# RP2040-M2-B-M-key.net
KiCad netlist of a schematic drawn in EAGLE
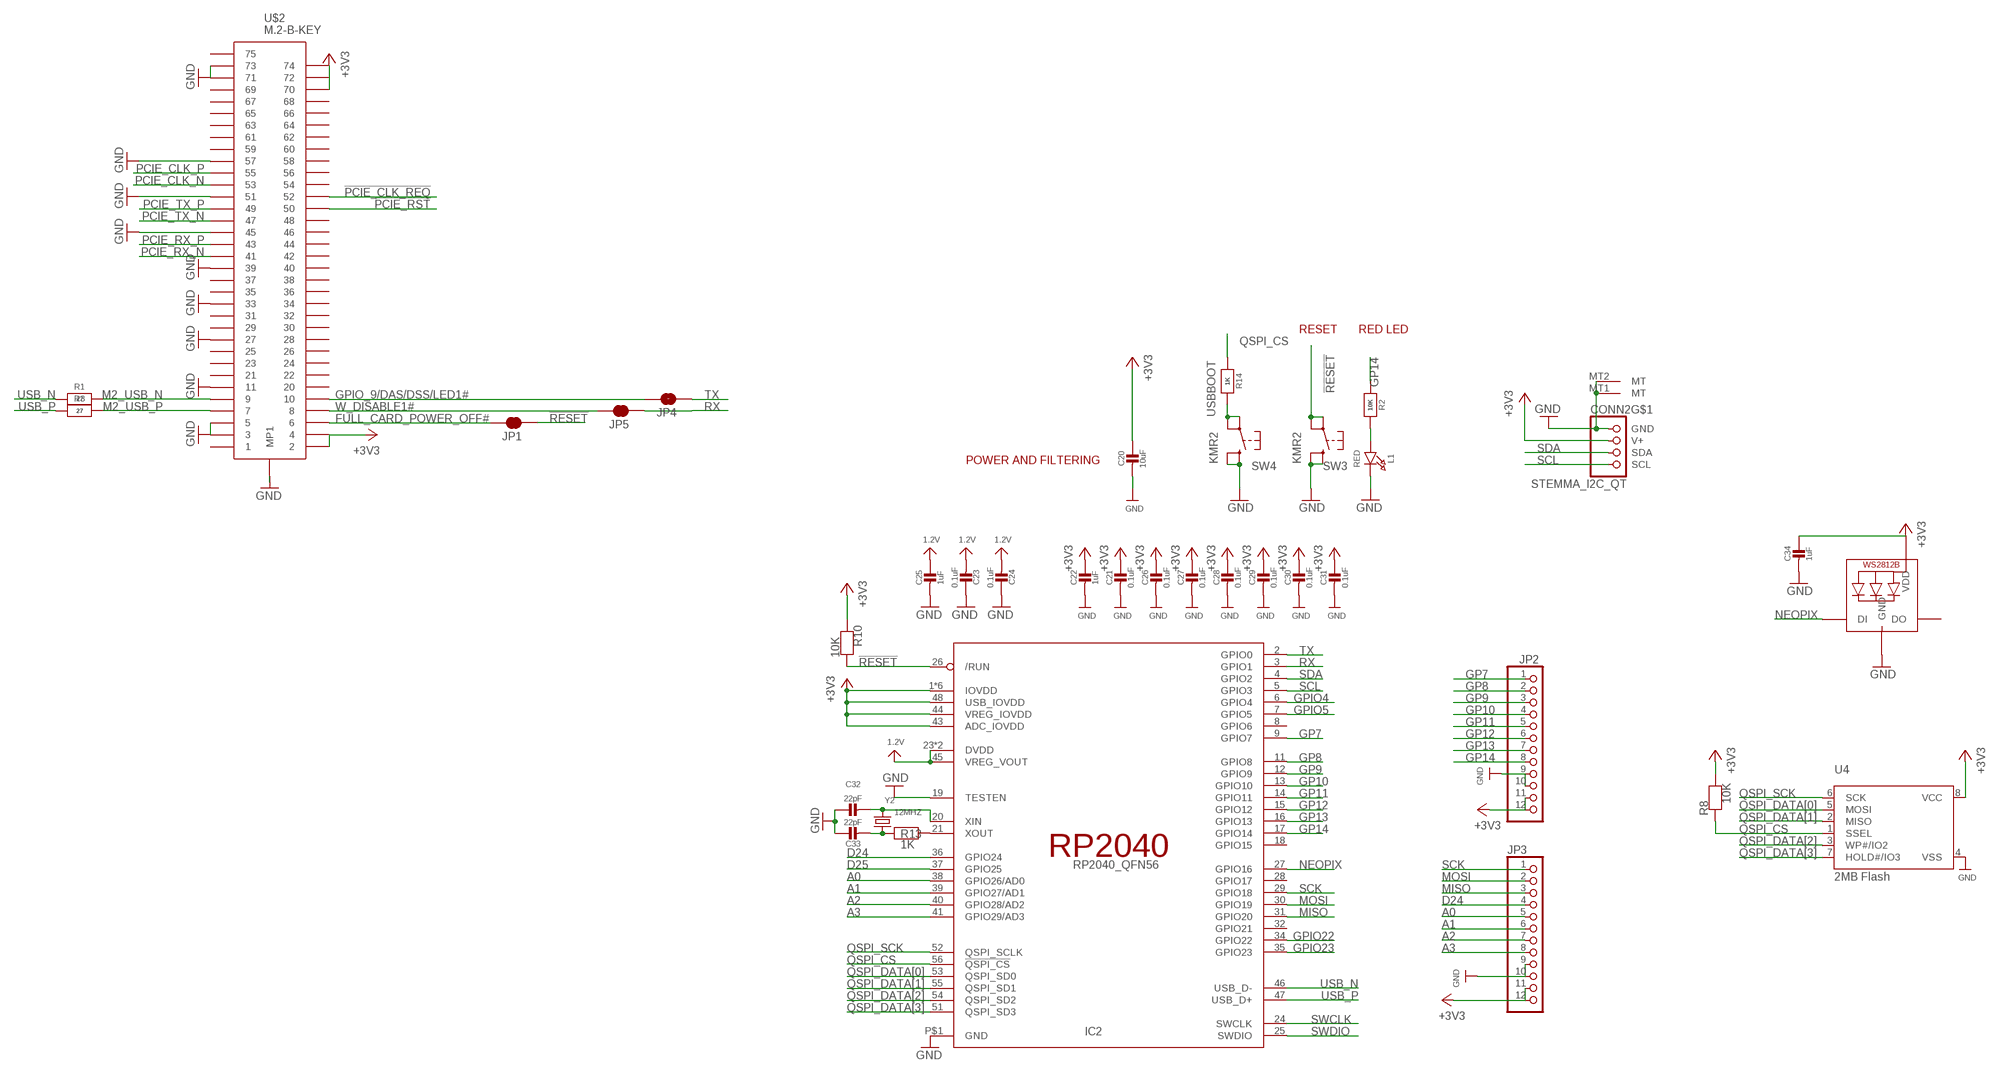
[diagram p0: schematic, sheet 1]

(export (version "E")
  (design (tool "Eeschema 10.0.6"))
  (components
    (comp (ref "C20")
      (value "10uF")
      (footprint "eagle-import:0805-NO")
      (libsource (lib "eagle-import") (part "CAP_CERAMIC0805-NOOUTLINE"))
    )
    (comp (ref "C21")
      (value "0.1uF")
      (footprint "eagle-import:_0402MP")
      (libsource (lib "eagle-import") (part "microbuilder_25095254_CAP_CERAMIC_0402MP"))
    )
    (comp (ref "C22")
      (value "1uF")
      (footprint "eagle-import:_0402MP")
      (libsource (lib "eagle-import") (part "microbuilder_25095254_CAP_CERAMIC_0402MP"))
    )
    (comp (ref "C23")
      (value "0.1uF")
      (footprint "eagle-import:_0402MP")
      (libsource (lib "eagle-import") (part "microbuilder_25095254_CAP_CERAMIC_0402MP"))
    )
    (comp (ref "C24")
      (value "0.1uF")
      (footprint "eagle-import:_0402MP")
      (libsource (lib "eagle-import") (part "microbuilder_25095254_CAP_CERAMIC_0402MP"))
    )
    (comp (ref "C25")
      (value "1uF")
      (footprint "eagle-import:_0402MP")
      (libsource (lib "eagle-import") (part "microbuilder_25095254_CAP_CERAMIC_0402MP"))
    )
    (comp (ref "C26")
      (value "0.1uF")
      (footprint "eagle-import:_0402MP")
      (libsource (lib "eagle-import") (part "microbuilder_25095254_CAP_CERAMIC_0402MP"))
    )
    (comp (ref "C27")
      (value "0.1uF")
      (footprint "eagle-import:_0402MP")
      (libsource (lib "eagle-import") (part "microbuilder_25095254_CAP_CERAMIC_0402MP"))
    )
    (comp (ref "C28")
      (value "0.1uF")
      (footprint "eagle-import:_0402MP")
      (libsource (lib "eagle-import") (part "microbuilder_25095254_CAP_CERAMIC_0402MP"))
    )
    (comp (ref "C29")
      (value "0.1uF")
      (footprint "eagle-import:_0402MP")
      (libsource (lib "eagle-import") (part "microbuilder_25095254_CAP_CERAMIC_0402MP"))
    )
    (comp (ref "C30")
      (value "0.1uF")
      (footprint "eagle-import:_0402MP")
      (libsource (lib "eagle-import") (part "microbuilder_25095254_CAP_CERAMIC_0402MP"))
    )
    (comp (ref "C31")
      (value "0.1uF")
      (footprint "eagle-import:_0402MP")
      (libsource (lib "eagle-import") (part "microbuilder_25095254_CAP_CERAMIC_0402MP"))
    )
    (comp (ref "C32")
      (value "22pF")
      (footprint "eagle-import:_0402MP")
      (libsource (lib "eagle-import") (part "microbuilder_25095254_CAP_CERAMIC_0402MP"))
    )
    (comp (ref "C33")
      (value "22pF")
      (footprint "eagle-import:_0402MP")
      (libsource (lib "eagle-import") (part "microbuilder_25095254_CAP_CERAMIC_0402MP"))
    )
    (comp (ref "C34")
      (value "1uF")
      (footprint "eagle-import:_0402MP")
      (libsource (lib "eagle-import") (part "microbuilder_25095254_CAP_CERAMIC_0402MP"))
    )
    (comp (ref "CONN2")
      (value "STEMMA_I2C_QT")
      (footprint "eagle-import:JST_SH4")
      (libsource (lib "eagle-import") (part "STEMMA_I2C_QT"))
    )
    (comp (ref "IC2")
      (value "RP2040_QFN56")
      (footprint "eagle-import:QFN56_7MM_REDUCEDEPAD")
      (libsource (lib "eagle-import") (part "RP2040_QFN56"))
    )
    (comp (ref "JP1")
      (value "JUMPER-SMT_2_NC_TRACE_NO-SILK")
      (footprint "eagle-import:SMT-JUMPER_2_NC_TRACE_NO-SILK")
      (libsource (lib "eagle-import") (part "JUMPER-SMT_2_NC_TRACE_NO-SILK"))
    )
    (comp (ref "JP2")
      (value "HEADER-1X12")
      (footprint "eagle-import:1X12_ROUND")
      (libsource (lib "eagle-import") (part "HEADER-1X12"))
    )
    (comp (ref "JP3")
      (value "HEADER-1X12")
      (footprint "eagle-import:1X12_ROUND")
      (libsource (lib "eagle-import") (part "HEADER-1X12"))
    )
    (comp (ref "JP4")
      (value "JUMPER-SMT_2_NC_TRACE_NO-SILK")
      (footprint "eagle-import:SMT-JUMPER_2_NC_TRACE_NO-SILK")
      (libsource (lib "eagle-import") (part "JUMPER-SMT_2_NC_TRACE_NO-SILK"))
    )
    (comp (ref "JP5")
      (value "JUMPER-SMT_2_NC_TRACE_NO-SILK")
      (footprint "eagle-import:SMT-JUMPER_2_NC_TRACE_NO-SILK")
      (libsource (lib "eagle-import") (part "JUMPER-SMT_2_NC_TRACE_NO-SILK"))
    )
    (comp (ref "L1")
      (value "RED")
      (footprint "eagle-import:CHIPLED_0603_NOOUTLINE")
      (libsource (lib "eagle-import") (part "LED0603_NOOUTLINE"))
    )
    (comp (ref "LED2")
      (value "WS2812B3535")
      (footprint "eagle-import:LED3535")
      (libsource (lib "eagle-import") (part "WS2812B3535"))
    )
    (comp (ref "R1")
      (value "27")
      (footprint "eagle-import:_0402MP")
      (libsource (lib "eagle-import") (part "RESISTOR_0402MP"))
    )
    (comp (ref "R2")
      (value "10K")
      (footprint "eagle-import:_0402MP")
      (libsource (lib "eagle-import") (part "RESISTOR_0402MP"))
    )
    (comp (ref "R3")
      (value "27")
      (footprint "eagle-import:_0402MP")
      (libsource (lib "eagle-import") (part "RESISTOR_0402MP"))
    )
    (comp (ref "R8")
      (value "10K")
      (footprint "eagle-import:_0402MP")
      (libsource (lib "eagle-import") (part "RESISTOR_0402MP"))
    )
    (comp (ref "R10")
      (value "10K")
      (footprint "eagle-import:_0402MP")
      (libsource (lib "eagle-import") (part "RESISTOR_0402MP"))
    )
    (comp (ref "R13")
      (value "1K")
      (footprint "eagle-import:_0402MP")
      (libsource (lib "eagle-import") (part "RESISTOR_0402MP"))
    )
    (comp (ref "R14")
      (value "1K")
      (footprint "eagle-import:_0402MP")
      (libsource (lib "eagle-import") (part "RESISTOR_0402MP"))
    )
    (comp (ref "SW3")
      (value "KMR2")
      (footprint "eagle-import:BTN_KMR2_4.6X2.8")
      (libsource (lib "eagle-import") (part "SWITCH_TACT_SMT4.6X2.8"))
    )
    (comp (ref "SW4")
      (value "KMR2")
      (footprint "eagle-import:BTN_KMR2_4.6X2.8")
      (libsource (lib "eagle-import") (part "SWITCH_TACT_SMT4.6X2.8"))
    )
    (comp (ref "U$2")
      (value "M.2-B-KEY")
      (footprint "eagle-import:M.2-B-KEY")
      (libsource (lib "eagle-import") (part "M.2-B-KEY"))
    )
    (comp (ref "U4")
      (value "2MB Flash")
      (footprint "eagle-import:SOIC8_208MIL")
      (libsource (lib "eagle-import") (part "SPIFLASH_8PIN208MIL"))
    )
    (comp (ref "Y2")
      (value "12MHZ")
      (footprint "eagle-import:CRYSTAL_3.2X2.5")
      (libsource (lib "eagle-import") (part "CRYSTALTHIN"))
    )
  )
  (nets
    (net (code "1") (name "+3V3") (class "Default")
      (node (ref "C20") (pin "1") (pinfunction "1_1") (pintype "passive"))
      (node (ref "C21") (pin "1") (pinfunction "P$1_1") (pintype "passive"))
      (node (ref "C22") (pin "1") (pinfunction "P$1_1") (pintype "passive"))
      (node (ref "C26") (pin "1") (pinfunction "P$1_1") (pintype "passive"))
      (node (ref "C27") (pin "1") (pinfunction "P$1_1") (pintype "passive"))
      (node (ref "C28") (pin "1") (pinfunction "P$1_1") (pintype "passive"))
      (node (ref "C29") (pin "1") (pinfunction "P$1_1") (pintype "passive"))
      (node (ref "C30") (pin "1") (pinfunction "P$1_1") (pintype "passive"))
      (node (ref "C31") (pin "1") (pinfunction "P$1_1") (pintype "passive"))
      (node (ref "C34") (pin "1") (pinfunction "P$1_1") (pintype "passive"))
      (node (ref "CONN2") (pin "2") (pinfunction "V+_2") (pintype "passive"))
      (node (ref "IC2") (pin "1") (pinfunction "IOVDD_1") (pintype "power_in"))
      (node (ref "IC2") (pin "10") (pinfunction "IOVDD_10") (pintype "power_in"))
      (node (ref "IC2") (pin "22") (pinfunction "IOVDD_22") (pintype "power_in"))
      (node (ref "IC2") (pin "33") (pinfunction "IOVDD_33") (pintype "power_in"))
      (node (ref "IC2") (pin "42") (pinfunction "IOVDD_42") (pintype "power_in"))
      (node (ref "IC2") (pin "43") (pinfunction "ADC_IOVDD_43") (pintype "power_in"))
      (node (ref "IC2") (pin "44") (pinfunction "VREG_IOVDD_44") (pintype "power_in"))
      (node (ref "IC2") (pin "48") (pinfunction "USB_IOVDD_48") (pintype "power_in"))
      (node (ref "IC2") (pin "49") (pinfunction "IOVDD_49") (pintype "power_in"))
      (node (ref "JP2") (pin "11") (pinfunction "11_11") (pintype "passive"))
      (node (ref "JP2") (pin "12") (pinfunction "12_12") (pintype "passive"))
      (node (ref "JP3") (pin "11") (pinfunction "11_11") (pintype "passive"))
      (node (ref "JP3") (pin "12") (pinfunction "12_12") (pintype "passive"))
      (node (ref "LED2") (pin "2") (pinfunction "VDD_2") (pintype "power_in"))
      (node (ref "R10") (pin "1") (pinfunction "1_1") (pintype "passive"))
      (node (ref "R8") (pin "2") (pinfunction "2_2") (pintype "passive"))
      (node (ref "U$2") (pin "P$2") (pinfunction "2_P$2") (pintype "bidirectional"))
      (node (ref "U$2") (pin "P$4") (pinfunction "4_P$4") (pintype "bidirectional"))
      (node (ref "U$2") (pin "P$70") (pinfunction "70_P$70") (pintype "bidirectional"))
      (node (ref "U$2") (pin "P$72") (pinfunction "72_P$72") (pintype "bidirectional"))
      (node (ref "U$2") (pin "P$74") (pinfunction "74_P$74") (pintype "bidirectional"))
      (node (ref "U4") (pin "8") (pinfunction "VCC_8") (pintype "bidirectional"))
    )
    (net (code "2") (name "/A0") (class "Default")
      (node (ref "IC2") (pin "38") (pinfunction "GPIO26/AD0_38") (pintype "bidirectional"))
      (node (ref "JP3") (pin "5") (pinfunction "5_5") (pintype "passive"))
    )
    (net (code "3") (name "/A1") (class "Default")
      (node (ref "IC2") (pin "39") (pinfunction "GPIO27/AD1_39") (pintype "bidirectional"))
      (node (ref "JP3") (pin "6") (pinfunction "6_6") (pintype "passive"))
    )
    (net (code "4") (name "/A2") (class "Default")
      (node (ref "IC2") (pin "40") (pinfunction "GPIO28/AD2_40") (pintype "bidirectional"))
      (node (ref "JP3") (pin "7") (pinfunction "7_7") (pintype "passive"))
    )
    (net (code "5") (name "/A3") (class "Default")
      (node (ref "IC2") (pin "41") (pinfunction "GPIO29/AD3_41") (pintype "bidirectional"))
      (node (ref "JP3") (pin "8") (pinfunction "8_8") (pintype "passive"))
    )
    (net (code "6") (name "/D24") (class "Default")
      (node (ref "IC2") (pin "36") (pinfunction "GPIO24_36") (pintype "bidirectional"))
      (node (ref "JP3") (pin "4") (pinfunction "4_4") (pintype "passive"))
    )
    (net (code "7") (name "/D25") (class "Default")
      (node (ref "IC2") (pin "37") (pinfunction "GPIO25_37") (pintype "bidirectional"))
    )
    (net (code "8") (name "/FULL_CARD_POWER_OFF#") (class "Default")
      (node (ref "JP1") (pin "1") (pinfunction "1_1") (pintype "passive"))
      (node (ref "U$2") (pin "P$6") (pinfunction "6_P$6") (pintype "bidirectional"))
    )
    (net (code "9") (name "/GP7") (class "Default")
      (node (ref "IC2") (pin "9") (pinfunction "GPIO7_9") (pintype "bidirectional"))
      (node (ref "JP2") (pin "1") (pinfunction "1_1") (pintype "passive"))
    )
    (net (code "10") (name "/GP8") (class "Default")
      (node (ref "IC2") (pin "11") (pinfunction "GPIO8_11") (pintype "bidirectional"))
      (node (ref "JP2") (pin "2") (pinfunction "2_2") (pintype "passive"))
    )
    (net (code "11") (name "/GP9") (class "Default")
      (node (ref "IC2") (pin "12") (pinfunction "GPIO9_12") (pintype "bidirectional"))
      (node (ref "JP2") (pin "3") (pinfunction "3_3") (pintype "passive"))
    )
    (net (code "12") (name "/GP10") (class "Default")
      (node (ref "IC2") (pin "13") (pinfunction "GPIO10_13") (pintype "bidirectional"))
      (node (ref "JP2") (pin "4") (pinfunction "4_4") (pintype "passive"))
    )
    (net (code "13") (name "/GP11") (class "Default")
      (node (ref "IC2") (pin "14") (pinfunction "GPIO11_14") (pintype "bidirectional"))
      (node (ref "JP2") (pin "5") (pinfunction "5_5") (pintype "passive"))
    )
    (net (code "14") (name "/GP12") (class "Default")
      (node (ref "IC2") (pin "15") (pinfunction "GPIO12_15") (pintype "bidirectional"))
      (node (ref "JP2") (pin "6") (pinfunction "6_6") (pintype "passive"))
    )
    (net (code "15") (name "/GP13") (class "Default")
      (node (ref "IC2") (pin "16") (pinfunction "GPIO13_16") (pintype "bidirectional"))
      (node (ref "JP2") (pin "7") (pinfunction "7_7") (pintype "passive"))
    )
    (net (code "16") (name "/GP14") (class "Default")
      (node (ref "IC2") (pin "17") (pinfunction "GPIO14_17") (pintype "bidirectional"))
      (node (ref "JP2") (pin "8") (pinfunction "8_8") (pintype "passive"))
      (node (ref "R2") (pin "1") (pinfunction "1_1") (pintype "passive"))
    )
    (net (code "17") (name "/GPIO4") (class "Default")
      (node (ref "IC2") (pin "6") (pinfunction "GPIO4_6") (pintype "bidirectional"))
    )
    (net (code "18") (name "/GPIO5") (class "Default")
      (node (ref "IC2") (pin "7") (pinfunction "GPIO5_7") (pintype "bidirectional"))
    )
    (net (code "19") (name "/GPIO22") (class "Default")
      (node (ref "IC2") (pin "34") (pinfunction "GPIO22_34") (pintype "bidirectional"))
    )
    (net (code "20") (name "/GPIO23") (class "Default")
      (node (ref "IC2") (pin "35") (pinfunction "GPIO23_35") (pintype "bidirectional"))
    )
    (net (code "21") (name "/GPIO_9{slash}DAS{slash}DSS{slash}LED1#") (class "Default")
      (node (ref "JP4") (pin "1") (pinfunction "1_1") (pintype "passive"))
      (node (ref "U$2") (pin "P$10") (pinfunction "10_P$10") (pintype "bidirectional"))
    )
    (net (code "22") (name "/M2_USB_N") (class "Default")
      (node (ref "R1") (pin "2") (pinfunction "2_2") (pintype "passive"))
      (node (ref "U$2") (pin "P$9") (pinfunction "9_P$9") (pintype "bidirectional"))
    )
    (net (code "23") (name "/M2_USB_P") (class "Default")
      (node (ref "R3") (pin "2") (pinfunction "2_2") (pintype "passive"))
      (node (ref "U$2") (pin "P$7") (pinfunction "7_P$7") (pintype "bidirectional"))
    )
    (net (code "24") (name "/MISO") (class "Default")
      (node (ref "IC2") (pin "31") (pinfunction "GPIO20_31") (pintype "bidirectional"))
      (node (ref "JP3") (pin "3") (pinfunction "3_3") (pintype "passive"))
    )
    (net (code "25") (name "/MOSI") (class "Default")
      (node (ref "IC2") (pin "30") (pinfunction "GPIO19_30") (pintype "bidirectional"))
      (node (ref "JP3") (pin "2") (pinfunction "2_2") (pintype "passive"))
    )
    (net (code "26") (name "/NEOPIX") (class "Default")
      (node (ref "IC2") (pin "27") (pinfunction "GPIO16_27") (pintype "bidirectional"))
      (node (ref "LED2") (pin "1") (pinfunction "DI_1") (pintype "input"))
    )
    (net (code "27") (name "/PCIE_CLK_N") (class "Default")
      (node (ref "U$2") (pin "P$53") (pinfunction "53_P$53") (pintype "bidirectional"))
    )
    (net (code "28") (name "/PCIE_CLK_P") (class "Default")
      (node (ref "U$2") (pin "P$55") (pinfunction "55_P$55") (pintype "bidirectional"))
    )
    (net (code "29") (name "/PCIE_RX_N") (class "Default")
      (node (ref "U$2") (pin "P$41") (pinfunction "41_P$41") (pintype "bidirectional"))
    )
    (net (code "30") (name "/PCIE_RX_P") (class "Default")
      (node (ref "U$2") (pin "P$43") (pinfunction "43_P$43") (pintype "bidirectional"))
    )
    (net (code "31") (name "/PCIE_TX_N") (class "Default")
      (node (ref "U$2") (pin "P$47") (pinfunction "47_P$47") (pintype "bidirectional"))
    )
    (net (code "32") (name "/PCIE_TX_P") (class "Default")
      (node (ref "U$2") (pin "P$49") (pinfunction "49_P$49") (pintype "bidirectional"))
    )
    (net (code "33") (name "/QSPI_CS") (class "Default")
      (node (ref "IC2") (pin "56") (pinfunction "~{QSPI_CS}_56") (pintype "bidirectional"))
      (node (ref "R14") (pin "1") (pinfunction "1_1") (pintype "passive"))
      (node (ref "R8") (pin "1") (pinfunction "1_1") (pintype "passive"))
      (node (ref "U4") (pin "1") (pinfunction "SSEL_1") (pintype "bidirectional"))
    )
    (net (code "34") (name "/QSPI_DATA[0]") (class "Default")
      (node (ref "IC2") (pin "53") (pinfunction "QSPI_SD0_53") (pintype "bidirectional"))
      (node (ref "U4") (pin "5") (pinfunction "MOSI_5") (pintype "bidirectional"))
    )
    (net (code "35") (name "/QSPI_DATA[1]") (class "Default")
      (node (ref "IC2") (pin "55") (pinfunction "QSPI_SD1_55") (pintype "bidirectional"))
      (node (ref "U4") (pin "2") (pinfunction "MISO_2") (pintype "bidirectional"))
    )
    (net (code "36") (name "/QSPI_DATA[2]") (class "Default")
      (node (ref "IC2") (pin "54") (pinfunction "QSPI_SD2_54") (pintype "bidirectional"))
      (node (ref "U4") (pin "3") (pinfunction "WP#/IO2_3") (pintype "bidirectional"))
    )
    (net (code "37") (name "/QSPI_DATA[3]") (class "Default")
      (node (ref "IC2") (pin "51") (pinfunction "QSPI_SD3_51") (pintype "bidirectional"))
      (node (ref "U4") (pin "7") (pinfunction "HOLD#/IO3_7") (pintype "bidirectional"))
    )
    (net (code "38") (name "/QSPI_SCK") (class "Default")
      (node (ref "IC2") (pin "52") (pinfunction "QSPI_SCLK_52") (pintype "bidirectional"))
      (node (ref "U4") (pin "6") (pinfunction "SCK_6") (pintype "bidirectional"))
    )
    (net (code "39") (name "/RX") (class "Default")
      (node (ref "IC2") (pin "3") (pinfunction "GPIO1_3") (pintype "bidirectional"))
      (node (ref "JP5") (pin "2") (pinfunction "2_2") (pintype "passive"))
    )
    (net (code "40") (name "/SCK") (class "Default")
      (node (ref "IC2") (pin "29") (pinfunction "GPIO18_29") (pintype "bidirectional"))
      (node (ref "JP3") (pin "1") (pinfunction "1_1") (pintype "passive"))
    )
    (net (code "41") (name "/SCL") (class "Default")
      (node (ref "CONN2") (pin "4") (pinfunction "SCL_4") (pintype "passive"))
      (node (ref "IC2") (pin "5") (pinfunction "GPIO3_5") (pintype "bidirectional"))
    )
    (net (code "42") (name "/SDA") (class "Default")
      (node (ref "CONN2") (pin "3") (pinfunction "SDA_3") (pintype "passive"))
      (node (ref "IC2") (pin "4") (pinfunction "GPIO2_4") (pintype "bidirectional"))
    )
    (net (code "43") (name "/SWCLK") (class "Default")
      (node (ref "IC2") (pin "24") (pinfunction "SWCLK_24") (pintype "bidirectional"))
    )
    (net (code "44") (name "/SWDIO") (class "Default")
      (node (ref "IC2") (pin "25") (pinfunction "SWDIO_25") (pintype "bidirectional"))
    )
    (net (code "45") (name "/TX") (class "Default")
      (node (ref "IC2") (pin "2") (pinfunction "GPIO0_2") (pintype "bidirectional"))
      (node (ref "JP4") (pin "2") (pinfunction "2_2") (pintype "passive"))
    )
    (net (code "46") (name "/USBBOOT") (class "Default")
      (node (ref "R14") (pin "2") (pinfunction "2_2") (pintype "passive"))
      (node (ref "SW4") (pin "A") (pinfunction "P_A") (pintype "passive"))
      (node (ref "SW4") (pin "A'") (pinfunction "P1_A'") (pintype "passive"))
    )
    (net (code "47") (name "/USB_N") (class "Default")
      (node (ref "IC2") (pin "46") (pinfunction "USB_D-_46") (pintype "bidirectional"))
      (node (ref "R1") (pin "1") (pinfunction "1_1") (pintype "passive"))
    )
    (net (code "48") (name "/USB_P") (class "Default")
      (node (ref "IC2") (pin "47") (pinfunction "USB_D+_47") (pintype "bidirectional"))
      (node (ref "R3") (pin "1") (pinfunction "1_1") (pintype "passive"))
    )
    (net (code "49") (name "/W_DISABLE1#") (class "Default")
      (node (ref "JP5") (pin "1") (pinfunction "1_1") (pintype "passive"))
      (node (ref "U$2") (pin "P$8") (pinfunction "8_P$8") (pintype "bidirectional"))
    )
    (net (code "50") (name "/~{PCIE_CLK_REQ}") (class "Default")
      (node (ref "U$2") (pin "P$52") (pinfunction "52_P$52") (pintype "bidirectional"))
    )
    (net (code "51") (name "/~{PCIE_RST}") (class "Default")
      (node (ref "U$2") (pin "P$50") (pinfunction "50_P$50") (pintype "bidirectional"))
    )
    (net (code "52") (name "/~{RESET}") (class "Default")
      (node (ref "IC2") (pin "26") (pinfunction "/RUN_26") (pintype "bidirectional"))
      (node (ref "JP1") (pin "2") (pinfunction "2_2") (pintype "passive"))
      (node (ref "R10") (pin "2") (pinfunction "2_2") (pintype "passive"))
      (node (ref "SW3") (pin "A") (pinfunction "P_A") (pintype "passive"))
      (node (ref "SW3") (pin "A'") (pinfunction "P1_A'") (pintype "passive"))
    )
    (net (code "53") (name "1.2V") (class "Default")
      (node (ref "C23") (pin "2") (pinfunction "P$2_2") (pintype "passive"))
      (node (ref "C24") (pin "2") (pinfunction "P$2_2") (pintype "passive"))
      (node (ref "C25") (pin "1") (pinfunction "P$1_1") (pintype "passive"))
      (node (ref "IC2") (pin "23") (pinfunction "DVDD_23") (pintype "power_in"))
      (node (ref "IC2") (pin "45") (pinfunction "VREG_VOUT_45") (pintype "power_in"))
      (node (ref "IC2") (pin "50") (pinfunction "DVDD_50") (pintype "power_in"))
    )
    (net (code "54") (name "GND") (class "Default")
      (node (ref "C20") (pin "2") (pinfunction "2_2") (pintype "passive"))
      (node (ref "C21") (pin "2") (pinfunction "P$2_2") (pintype "passive"))
      (node (ref "C22") (pin "2") (pinfunction "P$2_2") (pintype "passive"))
      (node (ref "C23") (pin "1") (pinfunction "P$1_1") (pintype "passive"))
      (node (ref "C24") (pin "1") (pinfunction "P$1_1") (pintype "passive"))
      (node (ref "C25") (pin "2") (pinfunction "P$2_2") (pintype "passive"))
      (node (ref "C26") (pin "2") (pinfunction "P$2_2") (pintype "passive"))
      (node (ref "C27") (pin "2") (pinfunction "P$2_2") (pintype "passive"))
      (node (ref "C28") (pin "2") (pinfunction "P$2_2") (pintype "passive"))
      (node (ref "C29") (pin "2") (pinfunction "P$2_2") (pintype "passive"))
      (node (ref "C30") (pin "2") (pinfunction "P$2_2") (pintype "passive"))
      (node (ref "C31") (pin "2") (pinfunction "P$2_2") (pintype "passive"))
      (node (ref "C32") (pin "1") (pinfunction "P$1_1") (pintype "passive"))
      (node (ref "C33") (pin "1") (pinfunction "P$1_1") (pintype "passive"))
      (node (ref "C34") (pin "2") (pinfunction "P$2_2") (pintype "passive"))
      (node (ref "CONN2") (pin "1") (pinfunction "GND_1") (pintype "passive"))
      (node (ref "CONN2") (pin "MT1") (pinfunction "MT_MT1") (pintype "bidirectional"))
      (node (ref "CONN2") (pin "MT2") (pinfunction "MT_MT2") (pintype "bidirectional"))
      (node (ref "IC2") (pin "19") (pinfunction "TESTEN_19") (pintype "input"))
      (node (ref "IC2") (pin "P$1") (pinfunction "GND_P$1") (pintype "power_in"))
      (node (ref "JP2") (pin "10") (pinfunction "10_10") (pintype "passive"))
      (node (ref "JP2") (pin "9") (pinfunction "9_9") (pintype "passive"))
      (node (ref "JP3") (pin "10") (pinfunction "10_10") (pintype "passive"))
      (node (ref "JP3") (pin "9") (pinfunction "9_9") (pintype "passive"))
      (node (ref "L1") (pin "C") (pinfunction "C_C") (pintype "passive"))
      (node (ref "LED2") (pin "4") (pinfunction "GND_4") (pintype "power_in"))
      (node (ref "SW3") (pin "B") (pinfunction "S_B") (pintype "passive"))
      (node (ref "SW3") (pin "B'") (pinfunction "S1_B'") (pintype "passive"))
      (node (ref "SW4") (pin "B") (pinfunction "S_B") (pintype "passive"))
      (node (ref "SW4") (pin "B'") (pinfunction "S1_B'") (pintype "passive"))
      (node (ref "U$2") (pin "MOUNTING-HOLE") (pinfunction "MP1_MOUNTING-HOLE") (pintype "bidirectional"))
      (node (ref "U$2") (pin "P$11") (pinfunction "11_P$11") (pintype "bidirectional"))
      (node (ref "U$2") (pin "P$27") (pinfunction "27_P$27") (pintype "bidirectional"))
      (node (ref "U$2") (pin "P$3") (pinfunction "3_P$3") (pintype "bidirectional"))
      (node (ref "U$2") (pin "P$33") (pinfunction "33_P$33") (pintype "bidirectional"))
      (node (ref "U$2") (pin "P$39") (pinfunction "39_P$39") (pintype "bidirectional"))
      (node (ref "U$2") (pin "P$45") (pinfunction "45_P$45") (pintype "bidirectional"))
      (node (ref "U$2") (pin "P$5") (pinfunction "5_P$5") (pintype "bidirectional"))
      (node (ref "U$2") (pin "P$51") (pinfunction "51_P$51") (pintype "bidirectional"))
      (node (ref "U$2") (pin "P$57") (pinfunction "57_P$57") (pintype "bidirectional"))
      (node (ref "U$2") (pin "P$71") (pinfunction "71_P$71") (pintype "bidirectional"))
      (node (ref "U$2") (pin "P$73") (pinfunction "73_P$73") (pintype "bidirectional"))
      (node (ref "U4") (pin "4") (pinfunction "VSS_4") (pintype "bidirectional"))
    )
    (net (code "55") (name "Net-(C32-P$2)") (class "Default")
      (node (ref "C32") (pin "2") (pinfunction "P$2_2") (pintype "passive"))
      (node (ref "IC2") (pin "20") (pinfunction "XIN_20") (pintype "input"))
      (node (ref "Y2") (pin "2") (pinfunction "2_2") (pintype "passive"))
    )
    (net (code "56") (name "Net-(C33-P$2)") (class "Default")
      (node (ref "C33") (pin "2") (pinfunction "P$2_2") (pintype "passive"))
      (node (ref "R13") (pin "1") (pinfunction "1_1") (pintype "passive"))
      (node (ref "Y2") (pin "1") (pinfunction "1_1") (pintype "passive"))
    )
    (net (code "57") (name "Net-(IC2-XOUT)") (class "Default")
      (node (ref "IC2") (pin "21") (pinfunction "XOUT_21") (pintype "output"))
      (node (ref "R13") (pin "2") (pinfunction "2_2") (pintype "passive"))
    )
    (net (code "58") (name "Net-(L1-PadA)") (class "Default")
      (node (ref "L1") (pin "A") (pinfunction "A_A") (pintype "passive"))
      (node (ref "R2") (pin "2") (pinfunction "2_2") (pintype "passive"))
    )
    (net (code "59") (name "unconnected-(IC2-GPIO6-Pad8)") (class "Default")
      (node (ref "IC2") (pin "8") (pinfunction "GPIO6_8") (pintype "bidirectional"))
    )
    (net (code "60") (name "unconnected-(IC2-GPIO15-Pad18)") (class "Default")
      (node (ref "IC2") (pin "18") (pinfunction "GPIO15_18") (pintype "bidirectional"))
    )
    (net (code "61") (name "unconnected-(IC2-GPIO17-Pad28)") (class "Default")
      (node (ref "IC2") (pin "28") (pinfunction "GPIO17_28") (pintype "bidirectional"))
    )
    (net (code "62") (name "unconnected-(IC2-GPIO21-Pad32)") (class "Default")
      (node (ref "IC2") (pin "32") (pinfunction "GPIO21_32") (pintype "bidirectional"))
    )
    (net (code "63") (name "unconnected-(LED2-DO-Pad3)") (class "Default")
      (node (ref "LED2") (pin "3") (pinfunction "DO_3") (pintype "output"))
    )
    (net (code "64") (name "unconnected-(U$2-1-PadP$1)") (class "Default")
      (node (ref "U$2") (pin "P$1") (pinfunction "1_P$1") (pintype "bidirectional"))
    )
    (net (code "65") (name "unconnected-(U$2-20-PadP$20)") (class "Default")
      (node (ref "U$2") (pin "P$20") (pinfunction "20_P$20") (pintype "bidirectional"))
    )
    (net (code "66") (name "unconnected-(U$2-21-PadP$21)") (class "Default")
      (node (ref "U$2") (pin "P$21") (pinfunction "21_P$21") (pintype "bidirectional"))
    )
    (net (code "67") (name "unconnected-(U$2-22-PadP$22)") (class "Default")
      (node (ref "U$2") (pin "P$22") (pinfunction "22_P$22") (pintype "bidirectional"))
    )
    (net (code "68") (name "unconnected-(U$2-23-PadP$23)") (class "Default")
      (node (ref "U$2") (pin "P$23") (pinfunction "23_P$23") (pintype "bidirectional"))
    )
    (net (code "69") (name "unconnected-(U$2-24-PadP$24)") (class "Default")
      (node (ref "U$2") (pin "P$24") (pinfunction "24_P$24") (pintype "bidirectional"))
    )
    (net (code "70") (name "unconnected-(U$2-25-PadP$25)") (class "Default")
      (node (ref "U$2") (pin "P$25") (pinfunction "25_P$25") (pintype "bidirectional"))
    )
    (net (code "71") (name "unconnected-(U$2-26-PadP$26)") (class "Default")
      (node (ref "U$2") (pin "P$26") (pinfunction "26_P$26") (pintype "bidirectional"))
    )
    (net (code "72") (name "unconnected-(U$2-28-PadP$28)") (class "Default")
      (node (ref "U$2") (pin "P$28") (pinfunction "28_P$28") (pintype "bidirectional"))
    )
    (net (code "73") (name "unconnected-(U$2-29-PadP$29)") (class "Default")
      (node (ref "U$2") (pin "P$29") (pinfunction "29_P$29") (pintype "bidirectional"))
    )
    (net (code "74") (name "unconnected-(U$2-30-PadP$30)") (class "Default")
      (node (ref "U$2") (pin "P$30") (pinfunction "30_P$30") (pintype "bidirectional"))
    )
    (net (code "75") (name "unconnected-(U$2-31-PadP$31)") (class "Default")
      (node (ref "U$2") (pin "P$31") (pinfunction "31_P$31") (pintype "bidirectional"))
    )
    (net (code "76") (name "unconnected-(U$2-32-PadP$32)") (class "Default")
      (node (ref "U$2") (pin "P$32") (pinfunction "32_P$32") (pintype "bidirectional"))
    )
    (net (code "77") (name "unconnected-(U$2-34-PadP$34)") (class "Default")
      (node (ref "U$2") (pin "P$34") (pinfunction "34_P$34") (pintype "bidirectional"))
    )
    (net (code "78") (name "unconnected-(U$2-35-PadP$35)") (class "Default")
      (node (ref "U$2") (pin "P$35") (pinfunction "35_P$35") (pintype "bidirectional"))
    )
    (net (code "79") (name "unconnected-(U$2-36-PadP$36)") (class "Default")
      (node (ref "U$2") (pin "P$36") (pinfunction "36_P$36") (pintype "bidirectional"))
    )
    (net (code "80") (name "unconnected-(U$2-37-PadP$37)") (class "Default")
      (node (ref "U$2") (pin "P$37") (pinfunction "37_P$37") (pintype "bidirectional"))
    )
    (net (code "81") (name "unconnected-(U$2-38-PadP$38)") (class "Default")
      (node (ref "U$2") (pin "P$38") (pinfunction "38_P$38") (pintype "bidirectional"))
    )
    (net (code "82") (name "unconnected-(U$2-40-PadP$40)") (class "Default")
      (node (ref "U$2") (pin "P$40") (pinfunction "40_P$40") (pintype "bidirectional"))
    )
    (net (code "83") (name "unconnected-(U$2-42-PadP$42)") (class "Default")
      (node (ref "U$2") (pin "P$42") (pinfunction "42_P$42") (pintype "bidirectional"))
    )
    (net (code "84") (name "unconnected-(U$2-44-PadP$44)") (class "Default")
      (node (ref "U$2") (pin "P$44") (pinfunction "44_P$44") (pintype "bidirectional"))
    )
    (net (code "85") (name "unconnected-(U$2-46-PadP$46)") (class "Default")
      (node (ref "U$2") (pin "P$46") (pinfunction "46_P$46") (pintype "bidirectional"))
    )
    (net (code "86") (name "unconnected-(U$2-48-PadP$48)") (class "Default")
      (node (ref "U$2") (pin "P$48") (pinfunction "48_P$48") (pintype "bidirectional"))
    )
    (net (code "87") (name "unconnected-(U$2-54-PadP$54)") (class "Default")
      (node (ref "U$2") (pin "P$54") (pinfunction "54_P$54") (pintype "bidirectional"))
    )
    (net (code "88") (name "unconnected-(U$2-56-PadP$56)") (class "Default")
      (node (ref "U$2") (pin "P$56") (pinfunction "56_P$56") (pintype "bidirectional"))
    )
    (net (code "89") (name "unconnected-(U$2-58-PadP$58)") (class "Default")
      (node (ref "U$2") (pin "P$58") (pinfunction "58_P$58") (pintype "bidirectional"))
    )
    (net (code "90") (name "unconnected-(U$2-59-PadP$59)") (class "Default")
      (node (ref "U$2") (pin "P$59") (pinfunction "59_P$59") (pintype "bidirectional"))
    )
    (net (code "91") (name "unconnected-(U$2-60-PadP$60)") (class "Default")
      (node (ref "U$2") (pin "P$60") (pinfunction "60_P$60") (pintype "bidirectional"))
    )
    (net (code "92") (name "unconnected-(U$2-61-PadP$61)") (class "Default")
      (node (ref "U$2") (pin "P$61") (pinfunction "61_P$61") (pintype "bidirectional"))
    )
    (net (code "93") (name "unconnected-(U$2-62-PadP$62)") (class "Default")
      (node (ref "U$2") (pin "P$62") (pinfunction "62_P$62") (pintype "bidirectional"))
    )
    (net (code "94") (name "unconnected-(U$2-63-PadP$63)") (class "Default")
      (node (ref "U$2") (pin "P$63") (pinfunction "63_P$63") (pintype "bidirectional"))
    )
    (net (code "95") (name "unconnected-(U$2-64-PadP$64)") (class "Default")
      (node (ref "U$2") (pin "P$64") (pinfunction "64_P$64") (pintype "bidirectional"))
    )
    (net (code "96") (name "unconnected-(U$2-65-PadP$65)") (class "Default")
      (node (ref "U$2") (pin "P$65") (pinfunction "65_P$65") (pintype "bidirectional"))
    )
    (net (code "97") (name "unconnected-(U$2-66-PadP$66)") (class "Default")
      (node (ref "U$2") (pin "P$66") (pinfunction "66_P$66") (pintype "bidirectional"))
    )
    (net (code "98") (name "unconnected-(U$2-67-PadP$67)") (class "Default")
      (node (ref "U$2") (pin "P$67") (pinfunction "67_P$67") (pintype "bidirectional"))
    )
    (net (code "99") (name "unconnected-(U$2-68-PadP$68)") (class "Default")
      (node (ref "U$2") (pin "P$68") (pinfunction "68_P$68") (pintype "bidirectional"))
    )
    (net (code "100") (name "unconnected-(U$2-69-PadP$69)") (class "Default")
      (node (ref "U$2") (pin "P$69") (pinfunction "69_P$69") (pintype "bidirectional"))
    )
    (net (code "101") (name "unconnected-(U$2-75-PadP$75)") (class "Default")
      (node (ref "U$2") (pin "P$75") (pinfunction "75_P$75") (pintype "bidirectional"))
    )
  )
)
